# Lab1_Kondrashova_USB_RS485.net
KiCad netlist of a schematic drawn in Altium Designer
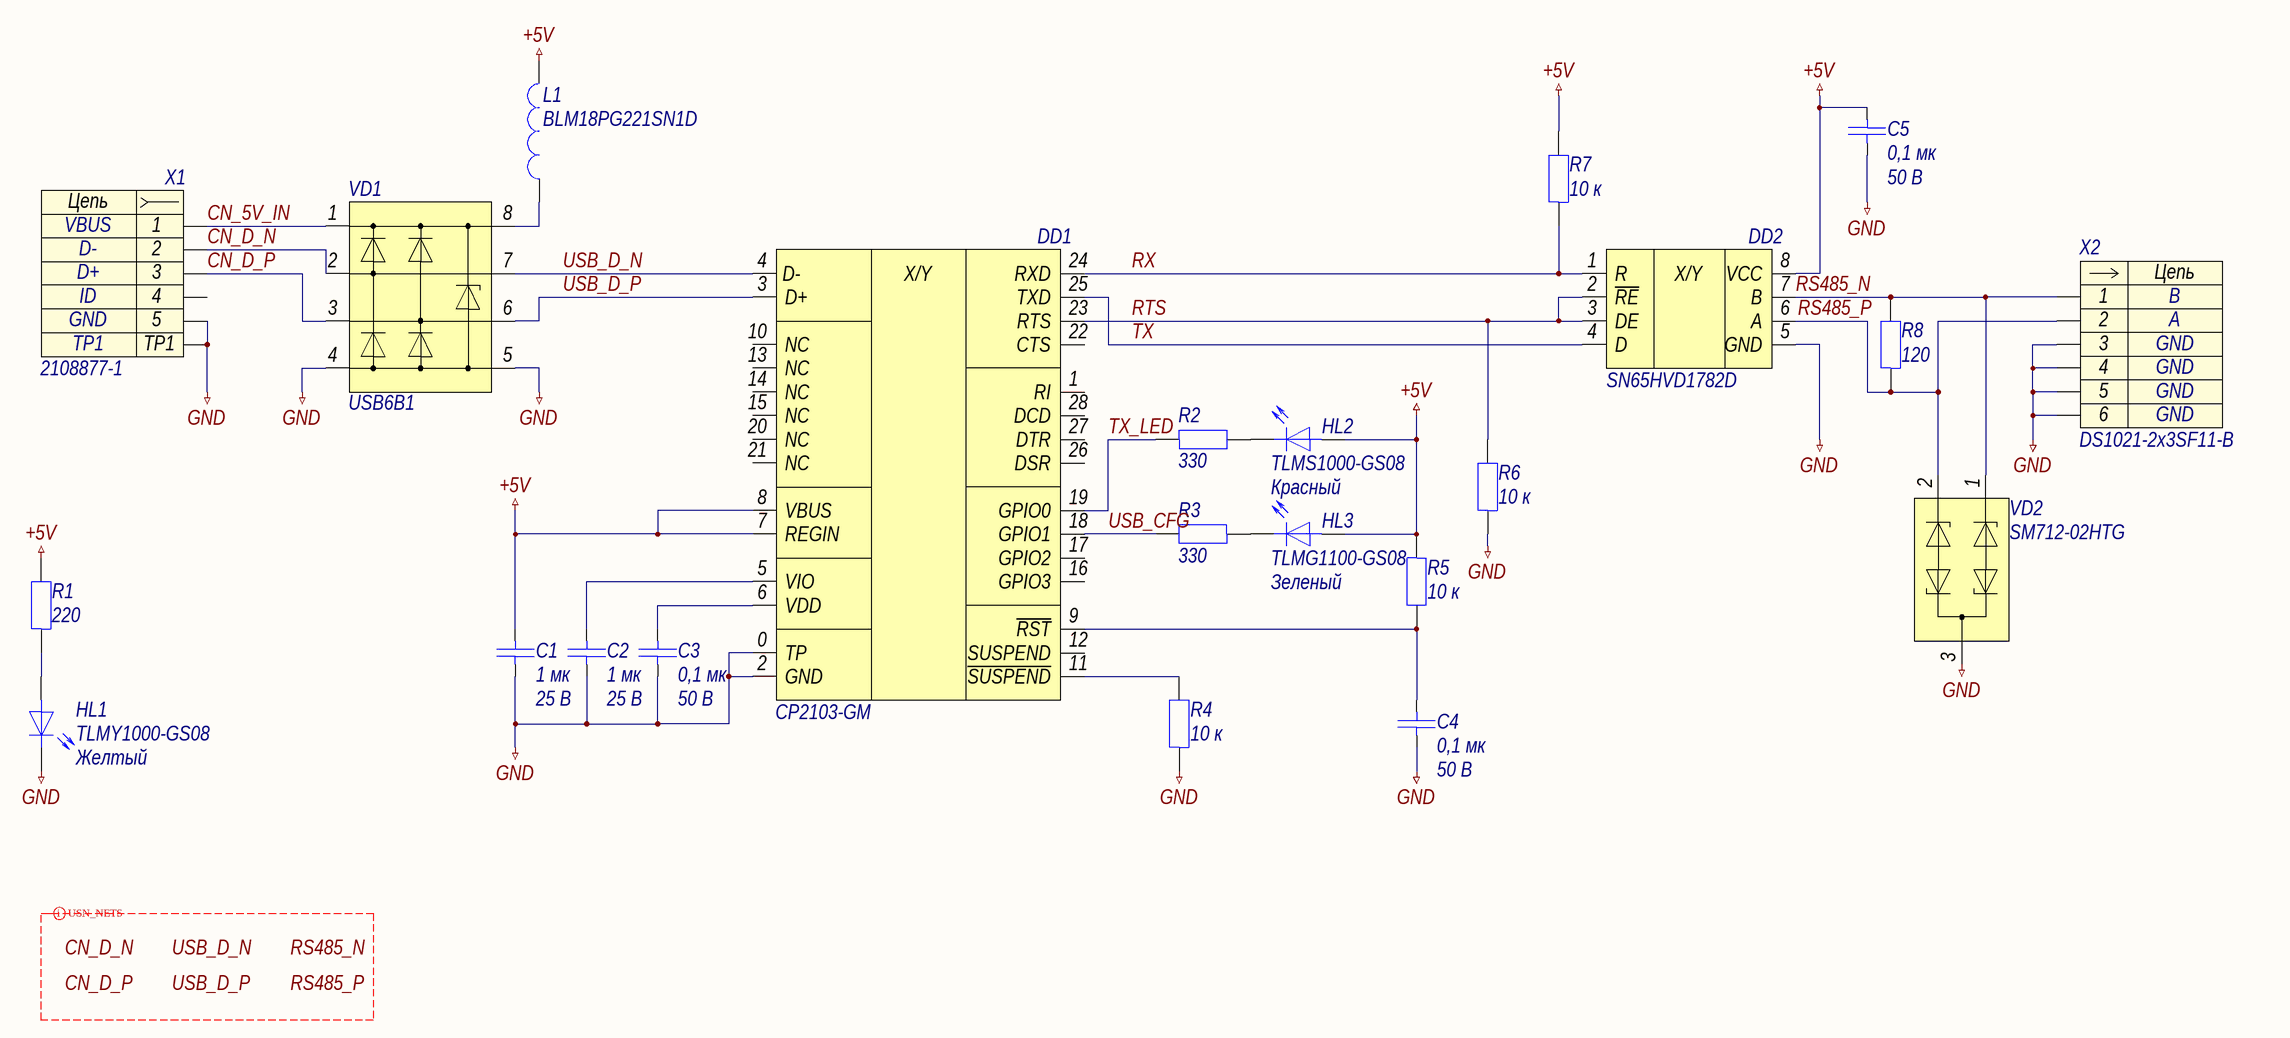
[diagram p0: Lab1_Kondrashova_USB_RS485.SchDoc]

(export (version "E")
  (design (tool "Eeschema 10.0.6"))
  (components
    (comp (ref "C1")
      (value "1 мк")
      (footprint "C0603")
      (description "=Описание")
      (fields (field (name "НАПРЯЖЕНИЕ") "25 В"))
      (libsource (lib "Database_Students") (part "C-NONPOLAR"))
    )
    (comp (ref "C2")
      (value "1 мк")
      (footprint "C0603")
      (description "=Описание")
      (fields (field (name "НАПРЯЖЕНИЕ") "25 В"))
      (libsource (lib "Database_Students") (part "C-NONPOLAR"))
    )
    (comp (ref "C3")
      (value "0,1 мк")
      (footprint "C0603")
      (description "=Описание")
      (fields (field (name "НАПРЯЖЕНИЕ") "50 В"))
      (libsource (lib "Database_Students") (part "C-NONPOLAR"))
    )
    (comp (ref "C4")
      (value "0,1 мк")
      (footprint "C0603")
      (description "=Описание")
      (fields (field (name "НАПРЯЖЕНИЕ") "50 В"))
      (libsource (lib "Database_Students") (part "C-NONPOLAR"))
    )
    (comp (ref "C5")
      (value "0,1 мк")
      (footprint "C0603")
      (description "=Описание")
      (fields (field (name "НАПРЯЖЕНИЕ") "50 В"))
      (libsource (lib "Database_Students") (part "C-NONPOLAR"))
    )
    (comp (ref "DD1")
      (value "CP2103-GM")
      (footprint "QFN-28-500X500X90")
      (description "=Описание")
      (libsource (lib "Database_Students") (part "CP2103-GM"))
    )
    (comp (ref "DD2")
      (value "SN65HVD1782D")
      (footprint "SOIC-8")
      (description "=Описание")
      (libsource (lib "Database_Students") (part "SN65HVD1782D"))
    )
    (comp (ref "HL1")
      (value "TLMY1000-GS08")
      (footprint "HL0603")
      (description "=Описание")
      (fields (field (name "COLOUR") "Желтый"))
      (libsource (lib "Database_Students") (part "LED-COMMON"))
    )
    (comp (ref "HL2")
      (value "TLMS1000-GS08")
      (footprint "HL0603")
      (description "=Описание")
      (fields (field (name "COLOUR") "Красный"))
      (libsource (lib "Database_Students") (part "LED-COMMON"))
    )
    (comp (ref "HL3")
      (value "TLMG1100-GS08")
      (footprint "HL0603")
      (description "=Описание")
      (fields (field (name "COLOUR") "Зеленый"))
      (libsource (lib "Database_Students") (part "LED-COMMON"))
    )
    (comp (ref "L1")
      (value "BLM18PG221SN1D")
      (footprint "BLM-2-0603")
      (description "=Описание")
      (libsource (lib "Database_Students") (part "FERRITE-BEAD"))
    )
    (comp (ref "R1")
      (value "220")
      (footprint "R0603")
      (description "=Описание")
      (libsource (lib "Database_Students") (part "R-COMMON"))
    )
    (comp (ref "R2")
      (value "330")
      (footprint "R0603")
      (description "=Описание")
      (libsource (lib "Database_Students") (part "R-COMMON"))
    )
    (comp (ref "R3")
      (value "330")
      (footprint "R0603")
      (description "=Описание")
      (libsource (lib "Database_Students") (part "R-COMMON"))
    )
    (comp (ref "R4")
      (value "10 к")
      (footprint "R0603")
      (description "=Описание")
      (libsource (lib "Database_Students") (part "R-COMMON"))
    )
    (comp (ref "R5")
      (value "10 к")
      (footprint "R0603")
      (description "=Описание")
      (libsource (lib "Database_Students") (part "R-COMMON"))
    )
    (comp (ref "R6")
      (value "10 к")
      (footprint "R0603")
      (description "=Описание")
      (libsource (lib "Database_Students") (part "R-COMMON"))
    )
    (comp (ref "R7")
      (value "10 к")
      (footprint "R0603")
      (description "=Описание")
      (libsource (lib "Database_Students") (part "R-COMMON"))
    )
    (comp (ref "R8")
      (value "120")
      (footprint "R0603")
      (description "=Описание")
      (libsource (lib "Database_Students") (part "R-COMMON"))
    )
    (comp (ref "VD1")
      (value "USB6B1")
      (footprint "SO-8")
      (description "=Описание")
      (libsource (lib "Database_Students") (part "USB6B1"))
    )
    (comp (ref "VD2")
      (value "SM712-02HTG")
      (footprint "SOT23-3")
      (description "=Описание")
      (libsource (lib "Database_Students") (part "SM712-02HTG"))
    )
    (comp (ref "X1")
      (value "2108877-1")
      (footprint "2108877-1")
      (description "=Описание")
      (libsource (lib "Database_Students") (part "HEADER-5-TP1-SCT"))
    )
    (comp (ref "X2")
      (value "DS1021-2x3SF11-B")
      (footprint "DS1021-2X3SF11-B")
      (description "=Описание")
      (libsource (lib "Database_Students") (part "HEADER-6-PLG"))
    )
  )
  (nets
    (net (code "1") (name "+5V") (class "Default")
      (node (ref "C1") (pin "1") (pinfunction "1_1") (pintype "passive"))
      (node (ref "C5") (pin "2") (pinfunction "2_2") (pintype "passive"))
      (node (ref "DD1") (pin "7") (pinfunction "REGIN_7") (pintype "passive"))
      (node (ref "DD1") (pin "8") (pinfunction "VBUS_8") (pintype "passive"))
      (node (ref "DD2") (pin "8") (pinfunction "VCC_8") (pintype "passive"))
      (node (ref "HL2") (pin "2") (pinfunction "2_2") (pintype "passive"))
      (node (ref "HL3") (pin "2") (pinfunction "2_2") (pintype "passive"))
      (node (ref "L1") (pin "2") (pinfunction "2_2") (pintype "passive"))
      (node (ref "R1") (pin "2") (pinfunction "2_2") (pintype "passive"))
      (node (ref "R5") (pin "1") (pinfunction "1_1") (pintype "passive"))
      (node (ref "R7") (pin "2") (pinfunction "2_2") (pintype "passive"))
    )
    (net (code "2") (name "/CN_5V_IN") (class "Default")
      (node (ref "VD1") (pin "1") (pinfunction "1_1") (pintype "passive"))
      (node (ref "X1") (pin "1") (pinfunction "1_1") (pintype "passive"))
    )
    (net (code "3") (name "/CN_D_N") (class "Default")
      (node (ref "VD1") (pin "2") (pinfunction "2_2") (pintype "passive"))
      (node (ref "X1") (pin "2") (pinfunction "2_2") (pintype "passive"))
    )
    (net (code "4") (name "/CN_D_P") (class "Default")
      (node (ref "VD1") (pin "3") (pinfunction "3_3") (pintype "passive"))
      (node (ref "X1") (pin "3") (pinfunction "3_3") (pintype "passive"))
    )
    (net (code "5") (name "/RS485_N") (class "Default")
      (node (ref "DD2") (pin "7") (pinfunction "B_7") (pintype "passive"))
      (node (ref "R8") (pin "2") (pinfunction "2_2") (pintype "passive"))
      (node (ref "VD2") (pin "1") (pinfunction "1_1") (pintype "passive"))
      (node (ref "X2") (pin "1") (pinfunction "1_1") (pintype "passive"))
    )
    (net (code "6") (name "/RS485_P") (class "Default")
      (node (ref "DD2") (pin "6") (pinfunction "A_6") (pintype "passive"))
      (node (ref "R8") (pin "1") (pinfunction "1_1") (pintype "passive"))
      (node (ref "VD2") (pin "2") (pinfunction "2_2") (pintype "passive"))
      (node (ref "X2") (pin "2") (pinfunction "2_2") (pintype "passive"))
    )
    (net (code "7") (name "/RTS") (class "Default")
      (node (ref "DD1") (pin "23") (pinfunction "RTS_23") (pintype "passive"))
      (node (ref "DD2") (pin "2") (pinfunction "~{RE}_2") (pintype "passive"))
      (node (ref "DD2") (pin "3") (pinfunction "DE_3") (pintype "passive"))
      (node (ref "R6") (pin "2") (pinfunction "2_2") (pintype "passive"))
    )
    (net (code "8") (name "/RX") (class "Default")
      (node (ref "DD1") (pin "24") (pinfunction "RXD_24") (pintype "passive"))
      (node (ref "DD2") (pin "1") (pinfunction "R_1") (pintype "passive"))
      (node (ref "R7") (pin "1") (pinfunction "1_1") (pintype "passive"))
    )
    (net (code "9") (name "/TX") (class "Default")
      (node (ref "DD1") (pin "25") (pinfunction "TXD_25") (pintype "passive"))
      (node (ref "DD2") (pin "4") (pinfunction "D_4") (pintype "passive"))
    )
    (net (code "10") (name "/TX_LED") (class "Default")
      (node (ref "DD1") (pin "19") (pinfunction "GPIO0_19") (pintype "passive"))
      (node (ref "R2") (pin "1") (pinfunction "1_1") (pintype "passive"))
    )
    (net (code "11") (name "/USB_CFG") (class "Default")
      (node (ref "DD1") (pin "18") (pinfunction "GPIO1_18") (pintype "passive"))
      (node (ref "R3") (pin "2") (pinfunction "2_2") (pintype "passive"))
    )
    (net (code "12") (name "/USB_D_N") (class "Default")
      (node (ref "DD1") (pin "4") (pinfunction "D-_4") (pintype "passive"))
      (node (ref "VD1") (pin "7") (pinfunction "7_7") (pintype "passive"))
    )
    (net (code "13") (name "/USB_D_P") (class "Default")
      (node (ref "DD1") (pin "3") (pinfunction "D+_3") (pintype "passive"))
      (node (ref "VD1") (pin "6") (pinfunction "6_6") (pintype "passive"))
    )
    (net (code "14") (name "GND") (class "Default")
      (node (ref "C1") (pin "2") (pinfunction "2_2") (pintype "passive"))
      (node (ref "C2") (pin "2") (pinfunction "2_2") (pintype "passive"))
      (node (ref "C3") (pin "2") (pinfunction "2_2") (pintype "passive"))
      (node (ref "C4") (pin "2") (pinfunction "2_2") (pintype "passive"))
      (node (ref "C5") (pin "1") (pinfunction "1_1") (pintype "passive"))
      (node (ref "DD1") (pin "0") (pinfunction "TP_0") (pintype "passive"))
      (node (ref "DD1") (pin "2") (pinfunction "GND_2") (pintype "passive"))
      (node (ref "DD2") (pin "5") (pinfunction "GND_5") (pintype "passive"))
      (node (ref "HL1") (pin "1") (pinfunction "1_1") (pintype "passive"))
      (node (ref "R4") (pin "1") (pinfunction "1_1") (pintype "passive"))
      (node (ref "R6") (pin "1") (pinfunction "1_1") (pintype "passive"))
      (node (ref "VD1") (pin "4") (pinfunction "4_4") (pintype "passive"))
      (node (ref "VD1") (pin "5") (pinfunction "5_5") (pintype "passive"))
      (node (ref "VD2") (pin "3") (pinfunction "3_3") (pintype "passive"))
      (node (ref "X1") (pin "5") (pinfunction "5_5") (pintype "passive"))
      (node (ref "X1") (pin "TP1") (pinfunction "TP1_TP1") (pintype "passive"))
      (node (ref "X2") (pin "3") (pinfunction "3_3") (pintype "passive"))
      (node (ref "X2") (pin "4") (pinfunction "4_4") (pintype "passive"))
      (node (ref "X2") (pin "5") (pinfunction "5_5") (pintype "passive"))
      (node (ref "X2") (pin "6") (pinfunction "6_6") (pintype "passive"))
    )
    (net (code "15") (name "Net-(DD1-VDD)") (class "Default")
      (node (ref "C3") (pin "1") (pinfunction "1_1") (pintype "passive"))
      (node (ref "DD1") (pin "6") (pinfunction "VDD_6") (pintype "passive"))
    )
    (net (code "16") (name "Net-(DD1-VIO)") (class "Default")
      (node (ref "C2") (pin "1") (pinfunction "1_1") (pintype "passive"))
      (node (ref "DD1") (pin "5") (pinfunction "VIO_5") (pintype "passive"))
    )
    (net (code "17") (name "Net-(DD1-~{RST})") (class "Default")
      (node (ref "C4") (pin "1") (pinfunction "1_1") (pintype "passive"))
      (node (ref "DD1") (pin "9") (pinfunction "~{RST}_9") (pintype "passive"))
      (node (ref "R5") (pin "2") (pinfunction "2_2") (pintype "passive"))
    )
    (net (code "18") (name "Net-(DD1-~{SUSPEND})") (class "Default")
      (node (ref "DD1") (pin "11") (pinfunction "~{SUSPEND}_11") (pintype "passive"))
      (node (ref "R4") (pin "2") (pinfunction "2_2") (pintype "passive"))
    )
    (net (code "19") (name "Net-(HL1-Pad2)") (class "Default")
      (node (ref "HL1") (pin "2") (pinfunction "2_2") (pintype "passive"))
      (node (ref "R1") (pin "1") (pinfunction "1_1") (pintype "passive"))
    )
    (net (code "20") (name "Net-(HL2-Pad1)") (class "Default")
      (node (ref "HL2") (pin "1") (pinfunction "1_1") (pintype "passive"))
      (node (ref "R2") (pin "2") (pinfunction "2_2") (pintype "passive"))
    )
    (net (code "21") (name "Net-(HL3-Pad1)") (class "Default")
      (node (ref "HL3") (pin "1") (pinfunction "1_1") (pintype "passive"))
      (node (ref "R3") (pin "1") (pinfunction "1_1") (pintype "passive"))
    )
    (net (code "22") (name "Net-(L1-Pad1)") (class "Default")
      (node (ref "L1") (pin "1") (pinfunction "1_1") (pintype "passive"))
      (node (ref "VD1") (pin "8") (pinfunction "8_8") (pintype "passive"))
    )
    (net (code "23") (name "unconnected-(DD1-CTS-Pad22)") (class "Default")
      (node (ref "DD1") (pin "22") (pinfunction "CTS_22") (pintype "passive"))
    )
    (net (code "24") (name "unconnected-(DD1-DCD-Pad28)") (class "Default")
      (node (ref "DD1") (pin "28") (pinfunction "DCD_28") (pintype "passive"))
    )
    (net (code "25") (name "unconnected-(DD1-DSR-Pad26)") (class "Default")
      (node (ref "DD1") (pin "26") (pinfunction "DSR_26") (pintype "passive"))
    )
    (net (code "26") (name "unconnected-(DD1-DTR-Pad27)") (class "Default")
      (node (ref "DD1") (pin "27") (pinfunction "DTR_27") (pintype "passive"))
    )
    (net (code "27") (name "unconnected-(DD1-GPIO2-Pad17)") (class "Default")
      (node (ref "DD1") (pin "17") (pinfunction "GPIO2_17") (pintype "passive"))
    )
    (net (code "28") (name "unconnected-(DD1-GPIO3-Pad16)") (class "Default")
      (node (ref "DD1") (pin "16") (pinfunction "GPIO3_16") (pintype "passive"))
    )
    (net (code "29") (name "unconnected-(DD1-NC-Pad10)") (class "Default")
      (node (ref "DD1") (pin "10") (pinfunction "NC_10") (pintype "passive"))
    )
    (net (code "30") (name "unconnected-(DD1-NC-Pad13)") (class "Default")
      (node (ref "DD1") (pin "13") (pinfunction "NC_13") (pintype "passive"))
    )
    (net (code "31") (name "unconnected-(DD1-NC-Pad14)") (class "Default")
      (node (ref "DD1") (pin "14") (pinfunction "NC_14") (pintype "passive"))
    )
    (net (code "32") (name "unconnected-(DD1-NC-Pad15)") (class "Default")
      (node (ref "DD1") (pin "15") (pinfunction "NC_15") (pintype "passive"))
    )
    (net (code "33") (name "unconnected-(DD1-NC-Pad20)") (class "Default")
      (node (ref "DD1") (pin "20") (pinfunction "NC_20") (pintype "passive"))
    )
    (net (code "34") (name "unconnected-(DD1-NC-Pad21)") (class "Default")
      (node (ref "DD1") (pin "21") (pinfunction "NC_21") (pintype "passive"))
    )
    (net (code "35") (name "unconnected-(DD1-RI-Pad1)") (class "Default")
      (node (ref "DD1") (pin "1") (pinfunction "RI_1") (pintype "passive"))
    )
    (net (code "36") (name "unconnected-(DD1-SUSPEND-Pad12)") (class "Default")
      (node (ref "DD1") (pin "12") (pinfunction "SUSPEND_12") (pintype "passive"))
    )
    (net (code "37") (name "unconnected-(X1-Pad4)") (class "Default")
      (node (ref "X1") (pin "4") (pinfunction "4_4") (pintype "passive"))
    )
  )
)
